# ZUM_Core_USB_BT.net
KiCad netlist of a schematic drawn in Altium Designer
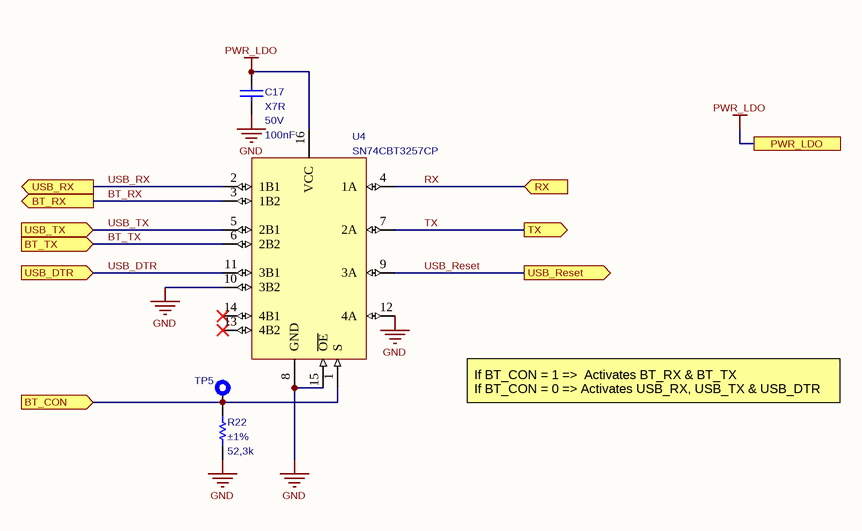
[diagram p0: ZUM_Core_USB_BT.SchDoc]

(export (version "E")
  (design (tool "Eeschema 10.0.6"))
  (components
    (comp (ref "C17")
      (value "C0603_100nF_50V_±10%_X7R")
      (footprint "C0603")
      (fields
        (field (name "DIELECTRIC") "X7R")
        (field (name "VOLTAGE") "50V")
        (field (name "CAPACITANCE") "100nF")
        (field (name "MANUFACTURER") "Kemet")
        (field (name "TOLERANCE") "±10%")
      )
      (libsource (lib "BQ Vault") (part "CMP-00257-1"))
    )
    (comp (ref "R22")
      (value "R0402_52,3k_0.063W_±1%")
      (footprint "R0402")
      (fields
        (field (name "TOLERANCE") "±1%")
        (field (name "POWER") "0.063W")
        (field (name "RESISTANCE") "52,3k")
        (field (name "MANUFACTURER") "Vishay")
      )
      (libsource (lib "BQ Vault") (part "Resistor"))
    )
    (comp (ref "TP5")
      (value "TP")
      (footprint "TP_POWER")
      (description "Testpoint 0.3mm")
      (fields (field (name "MANUFACTURER") "Oxley") (field (name "PART NUMBER") "TP_POWER"))
      (libsource (lib "BQ Vault") (part "CMP-A2499-3"))
    )
    (comp (ref "U4")
      (value "SN74CBT3257CP")
      (footprint "TSSOP16")
      (description "Multiplexer")
      (fields (field (name "MANUFACTURER") "Texas Instruments"))
      (libsource (lib "BQ Vault") (part "CMP-A2334-1"))
    )
  )
  (nets
    (net (code "1") (name "/BT_CON") (class "Default")
      (node (ref "R22") (pin "1") (pinfunction "1_1") (pintype "passive"))
      (node (ref "TP5") (pin "1") (pinfunction "1_1") (pintype "passive"))
      (node (ref "U4") (pin "1") (pinfunction "S_1") (pintype "input"))
    )
    (net (code "2") (name "/BT_RX") (class "Default")
      (node (ref "U4") (pin "3") (pinfunction "1B2_3") (pintype "bidirectional"))
    )
    (net (code "3") (name "/BT_TX") (class "Default")
      (node (ref "U4") (pin "6") (pinfunction "2B2_6") (pintype "bidirectional"))
    )
    (net (code "4") (name "/RX") (class "Default")
      (node (ref "U4") (pin "4") (pinfunction "1A_4") (pintype "bidirectional"))
    )
    (net (code "5") (name "/TX") (class "Default")
      (node (ref "U4") (pin "7") (pinfunction "2A_7") (pintype "bidirectional"))
    )
    (net (code "6") (name "/USB_DTR") (class "Default")
      (node (ref "U4") (pin "11") (pinfunction "3B1_11") (pintype "bidirectional"))
    )
    (net (code "7") (name "/USB_RX") (class "Default")
      (node (ref "U4") (pin "2") (pinfunction "1B1_2") (pintype "bidirectional"))
    )
    (net (code "8") (name "/USB_Reset") (class "Default")
      (node (ref "U4") (pin "9") (pinfunction "3A_9") (pintype "bidirectional"))
    )
    (net (code "9") (name "/USB_TX") (class "Default")
      (node (ref "U4") (pin "5") (pinfunction "2B1_5") (pintype "bidirectional"))
    )
    (net (code "10") (name "GND") (class "Default")
      (node (ref "C17") (pin "1") (pinfunction "1_1") (pintype "passive"))
      (node (ref "R22") (pin "2") (pinfunction "2_2") (pintype "passive"))
      (node (ref "U4") (pin "10") (pinfunction "3B2_10") (pintype "bidirectional"))
      (node (ref "U4") (pin "12") (pinfunction "4A_12") (pintype "bidirectional"))
      (node (ref "U4") (pin "15") (pinfunction "~{OE}_15") (pintype "input"))
      (node (ref "U4") (pin "8") (pinfunction "GND_8") (pintype "power_in"))
    )
    (net (code "11") (name "PWR_LDO") (class "Default")
      (node (ref "C17") (pin "2") (pinfunction "2_2") (pintype "passive"))
      (node (ref "U4") (pin "16") (pinfunction "VCC_16") (pintype "power_in"))
    )
    (net (code "12") (name "unconnected-(U4-4B1-Pad14)") (class "Default")
      (node (ref "U4") (pin "14") (pinfunction "4B1_14") (pintype "bidirectional+no_connect"))
    )
    (net (code "13") (name "unconnected-(U4-4B2-Pad13)") (class "Default")
      (node (ref "U4") (pin "13") (pinfunction "4B2_13") (pintype "bidirectional+no_connect"))
    )
  )
)
